# BreakoutBoard.net
KiCad netlist of a schematic drawn in Altium Designer
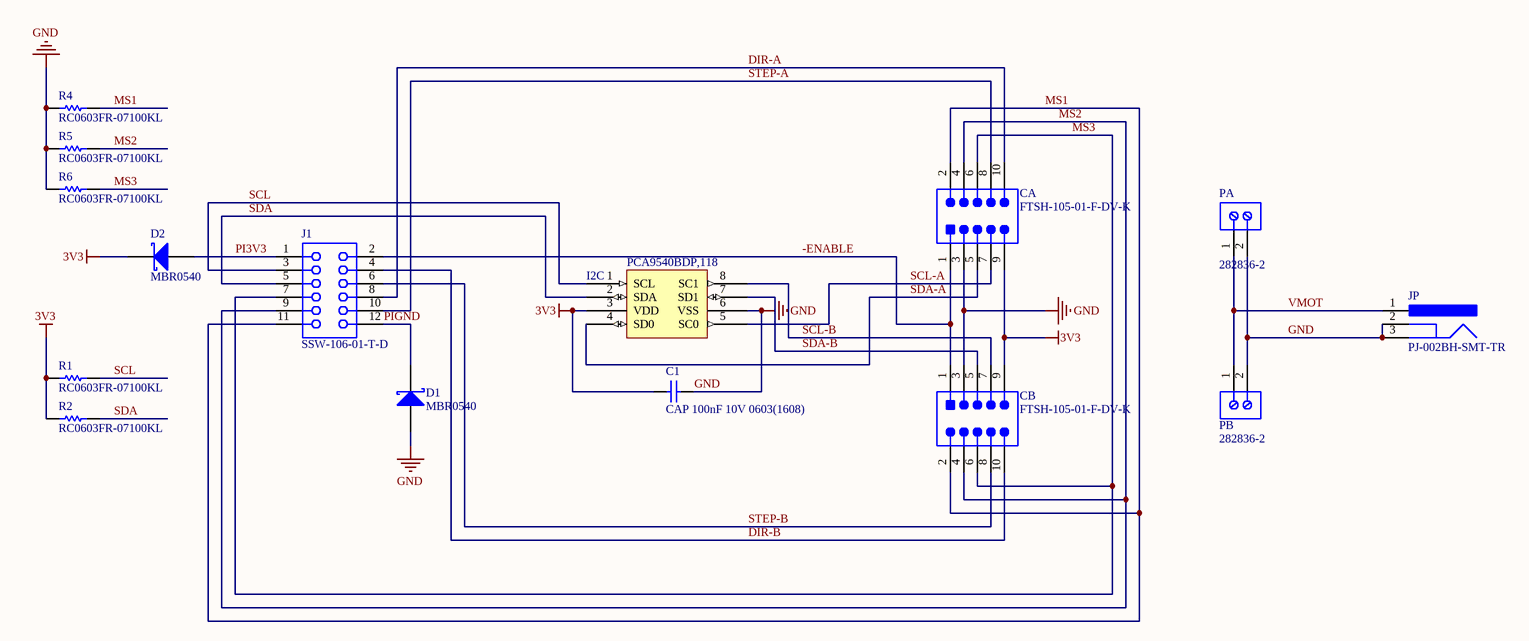
[diagram p0: BreakoutBoard.SchDoc]

(export (version "E")
  (design (tool "Eeschema 10.0.6"))
  (components
    (comp (ref "C1")
      (value "CAP 100nF 10V 0603(1608)")
      (footprint "CAPC0603(1608)100_M")
      (description "CAP 100nF 10V ±10% 0603 (1608 Metric) Thickness 1mm SMD")
      (fields (field (name "TOLERANCE") "Â±10%"))
      (libsource (lib "Altium Content Vault") (part "CAP"))
    )
    (comp (ref "CA")
      (value "FTSH-105-01-F-DV-K")
      (footprint "SMTC-FTSH-105-01-L-DV-K_V")
      (description "Male Header, Pitch 1.27 mm, 2 x 5 Position, Height 6.12 mm, RoHS, Tube")
      (fields (field (name "MANUFACTURER") "Samtec"))
      (libsource (lib "") (part "CN-2P-M-R10_1"))
    )
    (comp (ref "CB")
      (value "FTSH-105-01-F-DV-K")
      (footprint "SMTC-FTSH-105-01-L-DV-K_V")
      (description "Male Header, Pitch 1.27 mm, 2 x 5 Position, Height 6.12 mm, RoHS, Tube")
      (fields (field (name "MANUFACTURER") "Samtec"))
      (libsource (lib "Altium Content Vault") (part "CN-2P-M-R10"))
    )
    (comp (ref "D1")
      (value "MBR0540")
      (footprint "FAIR-SOD123-2_V")
      (description "Schottky Rectifier, 40 V, 0.5 A, 2-Pin SOD-123, RoHS, Tape and Reel")
      (fields (field (name "MANUFACTURER") "Fairchild"))
      (libsource (lib "Altium Content Vault") (part "DSKY-AK-2"))
    )
    (comp (ref "D2")
      (value "MBR0540")
      (footprint "FAIR-SOD123-2_V")
      (description "Schottky Rectifier, 40 V, 0.5 A, 2-Pin SOD-123, RoHS, Tape and Reel")
      (fields (field (name "MANUFACTURER") "Fairchild"))
      (libsource (lib "Altium Content Vault") (part "DSKY-AK-2"))
    )
    (comp (ref "I2C")
      (value "PCA9540BDP,118")
      (footprint "TSOP65P490X110-8N")
      (description "IC I2C MUX 2CH 8-TSSOP")
      (libsource (lib "BG Vault") (part "New symbol 1"))
    )
    (comp (ref "J1")
      (value "SSW-106-01-T-D")
      (footprint "SMTC-SSW-106-01-X-D")
      (description "SQ Post Socket, Through-hole, Vertical, -55 to 105 degC, 2.54mm Pitch, 12-Pin, Female, RoHS")
      (fields (field (name "MANUFACTURER") "Samtec"))
      (libsource (lib "Altium Content Vault") (part "SMTC-SSW-106-01-X-D"))
    )
    (comp (ref "JP")
      (value "PJ-002BH-SMT-TR")
      (footprint "CUI-PJ-002BH-SMT_V")
      (description "DC Power Jack, 24 V, -25 to 85 degC, 3-Pin SMD, RoHS, Bulk")
      (fields (field (name "MANUFACTURER") "CUIInc."))
      (libsource (lib "Altium Content Vault") (part "JACK-2CD3-RN"))
    )
    (comp (ref "PA")
      (value "282836-2")
      (footprint "TECO-282836-2_V")
      (description "Female Header, Pitch 5 mm, 1 x 2 Position, Height 10 mm, Tail Length 3.5 mm, Rohs, Bulk")
      (fields (field (name "VOLTAGE") "300V") (field (name "MANUFACTURER") "TE Connectivity"))
      (libsource (lib "Altium Content Vault") (part "CN-1P-F-TB2"))
    )
    (comp (ref "PB")
      (value "282836-2")
      (footprint "TECO-282836-2_V")
      (description "Female Header, Pitch 5 mm, 1 x 2 Position, Height 10 mm, Tail Length 3.5 mm, Rohs, Bulk")
      (fields (field (name "VOLTAGE") "300V") (field (name "MANUFACTURER") "TE Connectivity"))
      (libsource (lib "Altium Content Vault") (part "CN-1P-F-TB2"))
    )
    (comp (ref "R1")
      (value "RC0603FR-07100KL")
      (footprint "RESC1608X55X25ML10T15")
      (description "Chip Resistor, 100 KOhm, +/- 1%, 0.1 W, -55 to 155 degC, 0603 (1608 Metric), RoHS, Tape and Reel")
      (fields (field (name "MANUFACTURER") "Yageo") (field (name "TOLERANCE") "1%"))
      (libsource (lib "Altium Content Vault") (part "RES-2"))
    )
    (comp (ref "R2")
      (value "RC0603FR-07100KL")
      (footprint "RESC1608X55X25ML10T15")
      (description "Chip Resistor, 100 KOhm, +/- 1%, 0.1 W, -55 to 155 degC, 0603 (1608 Metric), RoHS, Tape and Reel")
      (fields (field (name "MANUFACTURER") "Yageo") (field (name "TOLERANCE") "1%"))
      (libsource (lib "Altium Content Vault") (part "RES-2"))
    )
    (comp (ref "R4")
      (value "RC0603FR-07100KL")
      (footprint "RESC1608X55X25ML10T15")
      (description "Chip Resistor, 100 KOhm, +/- 1%, 0.1 W, -55 to 155 degC, 0603 (1608 Metric), RoHS, Tape and Reel")
      (fields (field (name "MANUFACTURER") "Yageo") (field (name "TOLERANCE") "1%"))
      (libsource (lib "Altium Content Vault") (part "RES-2"))
    )
    (comp (ref "R5")
      (value "RC0603FR-07100KL")
      (footprint "RESC1608X55X25ML10T15")
      (description "Chip Resistor, 100 KOhm, +/- 1%, 0.1 W, -55 to 155 degC, 0603 (1608 Metric), RoHS, Tape and Reel")
      (fields (field (name "MANUFACTURER") "Yageo") (field (name "TOLERANCE") "1%"))
      (libsource (lib "Altium Content Vault") (part "RES-2"))
    )
    (comp (ref "R6")
      (value "RC0603FR-07100KL")
      (footprint "RESC1608X55X25ML10T15")
      (description "Chip Resistor, 100 KOhm, +/- 1%, 0.1 W, -55 to 155 degC, 0603 (1608 Metric), RoHS, Tape and Reel")
      (fields (field (name "MANUFACTURER") "Yageo") (field (name "TOLERANCE") "1%"))
      (libsource (lib "Altium Content Vault") (part "RES-2"))
    )
  )
  (nets
    (net (code "1") (name "/-ENABLE") (class "Default")
      (node (ref "CA") (pin "1") (pinfunction "1_1") (pintype "passive"))
      (node (ref "CB") (pin "1") (pinfunction "1_1") (pintype "passive"))
      (node (ref "J1") (pin "2") (pinfunction "2_2") (pintype "passive"))
    )
    (net (code "2") (name "/DIR-A") (class "Default")
      (node (ref "CA") (pin "10") (pinfunction "10_10") (pintype "passive"))
      (node (ref "J1") (pin "8") (pinfunction "8_8") (pintype "passive"))
    )
    (net (code "3") (name "/DIR-B") (class "Default")
      (node (ref "CB") (pin "10") (pinfunction "10_10") (pintype "passive"))
      (node (ref "J1") (pin "4") (pinfunction "4_4") (pintype "passive"))
    )
    (net (code "4") (name "/MS1") (class "Default")
      (node (ref "CA") (pin "2") (pinfunction "2_2") (pintype "passive"))
      (node (ref "CB") (pin "2") (pinfunction "2_2") (pintype "passive"))
      (node (ref "J1") (pin "11") (pinfunction "11_11") (pintype "passive"))
      (node (ref "R4") (pin "2") (pinfunction "2_2") (pintype "passive"))
    )
    (net (code "5") (name "/MS2") (class "Default")
      (node (ref "CA") (pin "4") (pinfunction "4_4") (pintype "passive"))
      (node (ref "CB") (pin "4") (pinfunction "4_4") (pintype "passive"))
      (node (ref "J1") (pin "9") (pinfunction "9_9") (pintype "passive"))
      (node (ref "R5") (pin "2") (pinfunction "2_2") (pintype "passive"))
    )
    (net (code "6") (name "/MS3") (class "Default")
      (node (ref "CA") (pin "6") (pinfunction "6_6") (pintype "passive"))
      (node (ref "CB") (pin "6") (pinfunction "6_6") (pintype "passive"))
      (node (ref "J1") (pin "7") (pinfunction "7_7") (pintype "passive"))
      (node (ref "R6") (pin "2") (pinfunction "2_2") (pintype "passive"))
    )
    (net (code "7") (name "/PI3V3") (class "Default")
      (node (ref "D2") (pin "1") (pinfunction "A_1") (pintype "passive"))
      (node (ref "J1") (pin "1") (pinfunction "1_1") (pintype "passive"))
    )
    (net (code "8") (name "/PIGND") (class "Default")
      (node (ref "D1") (pin "2") (pinfunction "K_2") (pintype "passive"))
      (node (ref "J1") (pin "12") (pinfunction "12_12") (pintype "passive"))
    )
    (net (code "9") (name "/SCL") (class "Default")
      (node (ref "I2C") (pin "1") (pinfunction "SCL_1") (pintype "input"))
      (node (ref "J1") (pin "3") (pinfunction "3_3") (pintype "passive"))
      (node (ref "R1") (pin "2") (pinfunction "2_2") (pintype "passive"))
    )
    (net (code "10") (name "/SCL-A") (class "Default")
      (node (ref "CA") (pin "7") (pinfunction "7_7") (pintype "passive"))
      (node (ref "I2C") (pin "5") (pinfunction "SC0_5") (pintype "output"))
    )
    (net (code "11") (name "/SCL-B") (class "Default")
      (node (ref "CB") (pin "7") (pinfunction "7_7") (pintype "passive"))
      (node (ref "I2C") (pin "8") (pinfunction "SC1_8") (pintype "output"))
    )
    (net (code "12") (name "/SDA") (class "Default")
      (node (ref "I2C") (pin "2") (pinfunction "SDA_2") (pintype "bidirectional"))
      (node (ref "J1") (pin "5") (pinfunction "5_5") (pintype "passive"))
      (node (ref "R2") (pin "2") (pinfunction "2_2") (pintype "passive"))
    )
    (net (code "13") (name "/SDA-A") (class "Default")
      (node (ref "CA") (pin "5") (pinfunction "5_5") (pintype "passive"))
      (node (ref "I2C") (pin "4") (pinfunction "SD0_4") (pintype "bidirectional"))
    )
    (net (code "14") (name "/SDA-B") (class "Default")
      (node (ref "CB") (pin "5") (pinfunction "5_5") (pintype "passive"))
      (node (ref "I2C") (pin "7") (pinfunction "SD1_7") (pintype "bidirectional"))
    )
    (net (code "15") (name "/STEP-A") (class "Default")
      (node (ref "CA") (pin "8") (pinfunction "8_8") (pintype "passive"))
      (node (ref "J1") (pin "10") (pinfunction "10_10") (pintype "passive"))
    )
    (net (code "16") (name "/STEP-B") (class "Default")
      (node (ref "CB") (pin "8") (pinfunction "8_8") (pintype "passive"))
      (node (ref "J1") (pin "6") (pinfunction "6_6") (pintype "passive"))
    )
    (net (code "17") (name "/VMOT") (class "Default")
      (node (ref "JP") (pin "1") (pinfunction "1_1") (pintype "passive"))
      (node (ref "PA") (pin "1") (pinfunction "1_1") (pintype "passive"))
      (node (ref "PB") (pin "1") (pinfunction "1_1") (pintype "passive"))
    )
    (net (code "18") (name "3V3") (class "Default")
      (node (ref "C1") (pin "1") (pinfunction "1_1") (pintype "passive"))
      (node (ref "CA") (pin "9") (pinfunction "9_9") (pintype "passive"))
      (node (ref "CB") (pin "9") (pinfunction "9_9") (pintype "passive"))
      (node (ref "D2") (pin "2") (pinfunction "K_2") (pintype "passive"))
      (node (ref "I2C") (pin "3") (pinfunction "VDD_3") (pintype "power_in"))
      (node (ref "R1") (pin "1") (pinfunction "1_1") (pintype "passive"))
      (node (ref "R2") (pin "1") (pinfunction "1_1") (pintype "passive"))
    )
    (net (code "19") (name "GND") (class "Default")
      (node (ref "C1") (pin "2") (pinfunction "2_2") (pintype "passive"))
      (node (ref "CA") (pin "3") (pinfunction "3_3") (pintype "passive"))
      (node (ref "CB") (pin "3") (pinfunction "3_3") (pintype "passive"))
      (node (ref "D1") (pin "1") (pinfunction "A_1") (pintype "passive"))
      (node (ref "I2C") (pin "6") (pinfunction "VSS_6") (pintype "power_in"))
      (node (ref "JP") (pin "2") (pinfunction "2_2") (pintype "passive"))
      (node (ref "JP") (pin "3") (pinfunction "3_3") (pintype "passive"))
      (node (ref "PA") (pin "2") (pinfunction "2_2") (pintype "passive"))
      (node (ref "PB") (pin "2") (pinfunction "2_2") (pintype "passive"))
      (node (ref "R4") (pin "1") (pinfunction "1_1") (pintype "passive"))
      (node (ref "R5") (pin "1") (pinfunction "1_1") (pintype "passive"))
      (node (ref "R6") (pin "1") (pinfunction "1_1") (pintype "passive"))
    )
  )
)
